# HARPY_SMD.net
KiCad netlist of a schematic drawn in EAGLE
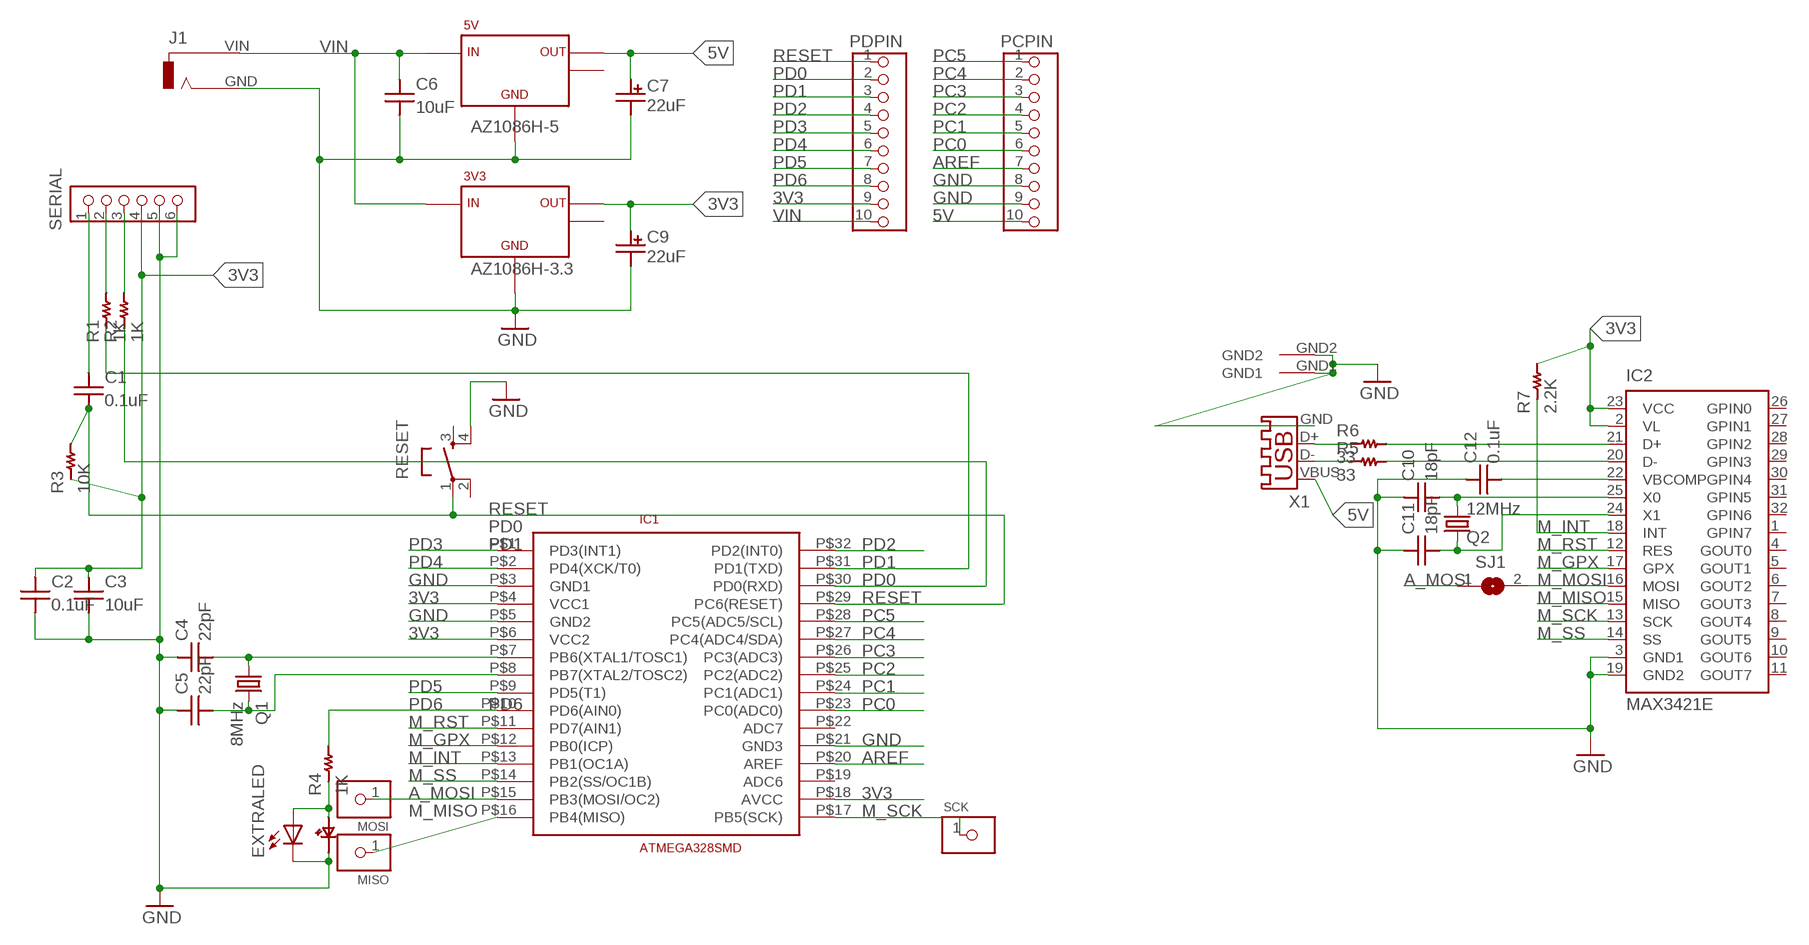
[diagram p0: schematic, sheet 1]

(export (version "E")
  (design (tool "Eeschema 10.0.6"))
  (components
    (comp (ref "3V3")
      (value "AZ1086H")
      (footprint "eagle-import:AZ1086H")
      (libsource (lib "eagle-import") (part "AZ1086H"))
    )
    (comp (ref "5V")
      (value "AZ1086H")
      (footprint "eagle-import:AZ1086H")
      (libsource (lib "eagle-import") (part "AZ1086H"))
    )
    (comp (ref "C1")
      (value "0.1uF")
      (footprint "eagle-import:SMD_2012_0805")
      (libsource (lib "eagle-import") (part "C_SMD2012"))
    )
    (comp (ref "C2")
      (value "0.1uF")
      (footprint "eagle-import:SMD_2012_0805")
      (libsource (lib "eagle-import") (part "C_SMD2012"))
    )
    (comp (ref "C3")
      (value "10uF")
      (footprint "eagle-import:SMD_2012_0805")
      (libsource (lib "eagle-import") (part "C_SMD2012"))
    )
    (comp (ref "C4")
      (value "22pF")
      (footprint "eagle-import:SMD_2012_0805")
      (libsource (lib "eagle-import") (part "C_SMD2012"))
    )
    (comp (ref "C5")
      (value "22pF")
      (footprint "eagle-import:SMD_2012_0805")
      (libsource (lib "eagle-import") (part "C_SMD2012"))
    )
    (comp (ref "C6")
      (value "10uF")
      (footprint "eagle-import:SMD_3216_1206")
      (libsource (lib "eagle-import") (part "C_SMD3216"))
    )
    (comp (ref "C7")
      (value "22uF")
      (footprint "eagle-import:SMD_3528")
      (libsource (lib "eagle-import") (part "C_SMD_POL3528"))
    )
    (comp (ref "C9")
      (value "22uF")
      (footprint "eagle-import:SMD_3528")
      (libsource (lib "eagle-import") (part "C_SMD_POL3528"))
    )
    (comp (ref "C10")
      (value "18pF")
      (footprint "eagle-import:SMD_2012_0805")
      (libsource (lib "eagle-import") (part "C_SMD2012"))
    )
    (comp (ref "C11")
      (value "18pF")
      (footprint "eagle-import:SMD_2012_0805")
      (libsource (lib "eagle-import") (part "C_SMD2012"))
    )
    (comp (ref "C12")
      (value "0.1uF")
      (footprint "eagle-import:SMD_2012_0805")
      (libsource (lib "eagle-import") (part "C_SMD2012"))
    )
    (comp (ref "EXTRALED")
      (value "LED3MM")
      (footprint "eagle-import:LED3MM")
      (libsource (lib "eagle-import") (part "LED3MM"))
    )
    (comp (ref "IC1")
      (value "ATMEGA328SMD")
      (footprint "eagle-import:ATMEGA328SMD")
      (libsource (lib "eagle-import") (part "ATMEGA328SMD"))
    )
    (comp (ref "IC2")
      (value "MAX3421E")
      (footprint "eagle-import:TQFP44")
      (libsource (lib "eagle-import") (part "2064VET44"))
    )
    (comp (ref "J1")
      (value "DCJ0303")
      (footprint "eagle-import:DCJ0303")
      (libsource (lib "eagle-import") (part "DCJ0303"))
    )
    (comp (ref "LED")
      (value "LED1608")
      (footprint "eagle-import:SMD_1608_0603")
      (libsource (lib "eagle-import") (part "LED1608"))
    )
    (comp (ref "MISO")
      (value "1X0108S")
      (footprint "eagle-import:1X01_0.8_UNSIGNED_SQUARE")
      (libsource (lib "eagle-import") (part "1X0108S"))
    )
    (comp (ref "MOSI")
      (value "1X0108S")
      (footprint "eagle-import:1X01_0.8_UNSIGNED_SQUARE")
      (libsource (lib "eagle-import") (part "1X0108S"))
    )
    (comp (ref "PCPIN")
      (value "1X10")
      (footprint "eagle-import:1X10_1.1_UNSIGNED")
      (libsource (lib "eagle-import") (part "1X10"))
    )
    (comp (ref "PDPIN")
      (value "1X10")
      (footprint "eagle-import:1X10_1.1_UNSIGNED")
      (libsource (lib "eagle-import") (part "1X10"))
    )
    (comp (ref "Q1")
      (value "8MHz")
      (footprint "eagle-import:HC49U-V")
      (libsource (lib "eagle-import") (part "CRYSTALHC49U-V"))
    )
    (comp (ref "Q2")
      (value "12MHz")
      (footprint "eagle-import:HC49U-V")
      (libsource (lib "eagle-import") (part "CRYSTALHC49U-V"))
    )
    (comp (ref "R1")
      (value "1K")
      (footprint "eagle-import:SMD_2012_0805")
      (libsource (lib "eagle-import") (part "R_SMD2012"))
    )
    (comp (ref "R2")
      (value "1K")
      (footprint "eagle-import:SMD_2012_0805")
      (libsource (lib "eagle-import") (part "R_SMD2012"))
    )
    (comp (ref "R3")
      (value "10K")
      (footprint "eagle-import:SMD_2012_0805")
      (libsource (lib "eagle-import") (part "R_SMD2012"))
    )
    (comp (ref "R4")
      (value "1K")
      (footprint "eagle-import:SMD_2012_0805")
      (libsource (lib "eagle-import") (part "R_SMD2012"))
    )
    (comp (ref "R5")
      (value "33")
      (footprint "eagle-import:SMD_2012_0805")
      (libsource (lib "eagle-import") (part "R_SMD2012"))
    )
    (comp (ref "R6")
      (value "33")
      (footprint "eagle-import:SMD_2012_0805")
      (libsource (lib "eagle-import") (part "R_SMD2012"))
    )
    (comp (ref "R7")
      (value "2.2K")
      (footprint "eagle-import:SMD_2012_0805")
      (libsource (lib "eagle-import") (part "R_SMD2012"))
    )
    (comp (ref "RESET")
      (value "10-XXAKI")
      (footprint "eagle-import:TSKB-2JL")
      (libsource (lib "eagle-import") (part "10-XXAKI"))
    )
    (comp (ref "SCK")
      (value "1X0108S")
      (footprint "eagle-import:1X01_0.8_UNSIGNED_SQUARE")
      (libsource (lib "eagle-import") (part "1X0108S"))
    )
    (comp (ref "SERIAL")
      (value "1X06A")
      (footprint "eagle-import:1X06_1.1_ARROW")
      (libsource (lib "eagle-import") (part "1X06A"))
    )
    (comp (ref "SJ1") (value "SJ") (footprint "eagle-import:SJ") (libsource (lib "eagle-import") (part "SJ")))
    (comp (ref "X1")
      (value "USB-A003")
      (footprint "eagle-import:USB-A003")
      (libsource (lib "eagle-import") (part "USB-A003"))
    )
  )
  (nets
    (net (code "1") (name "/AREF") (class "Default")
      (node (ref "IC1") (pin "P$20") (pinfunction "AREF_P$20") (pintype "bidirectional"))
      (node (ref "PCPIN") (pin "7") (pinfunction "7_7") (pintype "passive"))
    )
    (net (code "2") (name "/A_MOSI") (class "Default")
      (node (ref "IC1") (pin "P$15") (pinfunction "PB3(MOSI/OC2)_P$15") (pintype "bidirectional"))
      (node (ref "MOSI") (pin "1") (pinfunction "1_1") (pintype "passive"))
      (node (ref "SJ1") (pin "1") (pinfunction "1_1") (pintype "passive"))
    )
    (net (code "3") (name "/M_GPX") (class "Default")
      (node (ref "IC1") (pin "P$12") (pinfunction "PB0(ICP)_P$12") (pintype "bidirectional"))
      (node (ref "IC2") (pin "17") (pinfunction "GPX_17") (pintype "bidirectional"))
    )
    (net (code "4") (name "/M_INT") (class "Default")
      (node (ref "IC1") (pin "P$13") (pinfunction "PB1(OC1A)_P$13") (pintype "bidirectional"))
      (node (ref "IC2") (pin "18") (pinfunction "INT_18") (pintype "bidirectional"))
      (node (ref "R7") (pin "P$1") (pinfunction "1_P$1") (pintype "bidirectional"))
    )
    (net (code "5") (name "/M_MISO") (class "Default")
      (node (ref "IC1") (pin "P$16") (pinfunction "PB4(MISO)_P$16") (pintype "bidirectional"))
      (node (ref "IC2") (pin "15") (pinfunction "MISO_15") (pintype "bidirectional"))
      (node (ref "MISO") (pin "1") (pinfunction "1_1") (pintype "passive"))
    )
    (net (code "6") (name "/M_MOSI") (class "Default")
      (node (ref "IC2") (pin "16") (pinfunction "MOSI_16") (pintype "bidirectional"))
      (node (ref "SJ1") (pin "2") (pinfunction "2_2") (pintype "passive"))
    )
    (net (code "7") (name "/M_RST") (class "Default")
      (node (ref "IC1") (pin "P$11") (pinfunction "PD7(AIN1)_P$11") (pintype "bidirectional"))
      (node (ref "IC2") (pin "12") (pinfunction "RES_12") (pintype "bidirectional"))
    )
    (net (code "8") (name "/M_SCK") (class "Default")
      (node (ref "IC1") (pin "P$17") (pinfunction "PB5(SCK)_P$17") (pintype "bidirectional"))
      (node (ref "IC2") (pin "13") (pinfunction "SCK_13") (pintype "bidirectional"))
      (node (ref "SCK") (pin "1") (pinfunction "1_1") (pintype "passive"))
    )
    (net (code "9") (name "/M_SS") (class "Default")
      (node (ref "IC1") (pin "P$14") (pinfunction "PB2(SS/OC1B)_P$14") (pintype "bidirectional"))
      (node (ref "IC2") (pin "14") (pinfunction "SS_14") (pintype "bidirectional"))
    )
    (net (code "10") (name "/PC0") (class "Default")
      (node (ref "IC1") (pin "P$23") (pinfunction "PC0(ADC0)_P$23") (pintype "bidirectional"))
      (node (ref "PCPIN") (pin "6") (pinfunction "6_6") (pintype "passive"))
    )
    (net (code "11") (name "/PC1") (class "Default")
      (node (ref "IC1") (pin "P$24") (pinfunction "PC1(ADC1)_P$24") (pintype "bidirectional"))
      (node (ref "PCPIN") (pin "5") (pinfunction "5_5") (pintype "passive"))
    )
    (net (code "12") (name "/PC2") (class "Default")
      (node (ref "IC1") (pin "P$25") (pinfunction "PC2(ADC2)_P$25") (pintype "bidirectional"))
      (node (ref "PCPIN") (pin "4") (pinfunction "4_4") (pintype "passive"))
    )
    (net (code "13") (name "/PC3") (class "Default")
      (node (ref "IC1") (pin "P$26") (pinfunction "PC3(ADC3)_P$26") (pintype "bidirectional"))
      (node (ref "PCPIN") (pin "3") (pinfunction "3_3") (pintype "passive"))
    )
    (net (code "14") (name "/PC4") (class "Default")
      (node (ref "IC1") (pin "P$27") (pinfunction "PC4(ADC4/SDA)_P$27") (pintype "bidirectional"))
      (node (ref "PCPIN") (pin "2") (pinfunction "2_2") (pintype "passive"))
    )
    (net (code "15") (name "/PC5") (class "Default")
      (node (ref "IC1") (pin "P$28") (pinfunction "PC5(ADC5/SCL)_P$28") (pintype "bidirectional"))
      (node (ref "PCPIN") (pin "1") (pinfunction "1_1") (pintype "passive"))
    )
    (net (code "16") (name "/PD0") (class "Default")
      (node (ref "IC1") (pin "P$30") (pinfunction "PD0(RXD)_P$30") (pintype "bidirectional"))
      (node (ref "PDPIN") (pin "2") (pinfunction "2_2") (pintype "passive"))
      (node (ref "R2") (pin "P$1") (pinfunction "1_P$1") (pintype "bidirectional"))
    )
    (net (code "17") (name "/PD1") (class "Default")
      (node (ref "IC1") (pin "P$31") (pinfunction "PD1(TXD)_P$31") (pintype "bidirectional"))
      (node (ref "PDPIN") (pin "3") (pinfunction "3_3") (pintype "passive"))
      (node (ref "R1") (pin "P$1") (pinfunction "1_P$1") (pintype "bidirectional"))
    )
    (net (code "18") (name "/PD2") (class "Default")
      (node (ref "IC1") (pin "P$32") (pinfunction "PD2(INT0)_P$32") (pintype "bidirectional"))
      (node (ref "PDPIN") (pin "4") (pinfunction "4_4") (pintype "passive"))
    )
    (net (code "19") (name "/PD3") (class "Default")
      (node (ref "IC1") (pin "P$1") (pinfunction "PD3(INT1)_P$1") (pintype "bidirectional"))
      (node (ref "PDPIN") (pin "5") (pinfunction "5_5") (pintype "passive"))
    )
    (net (code "20") (name "/PD4") (class "Default")
      (node (ref "IC1") (pin "P$2") (pinfunction "PD4(XCK/T0)_P$2") (pintype "bidirectional"))
      (node (ref "PDPIN") (pin "6") (pinfunction "6_6") (pintype "passive"))
    )
    (net (code "21") (name "/PD5") (class "Default")
      (node (ref "IC1") (pin "P$9") (pinfunction "PD5(T1)_P$9") (pintype "bidirectional"))
      (node (ref "PDPIN") (pin "7") (pinfunction "7_7") (pintype "passive"))
    )
    (net (code "22") (name "/PD6") (class "Default")
      (node (ref "IC1") (pin "P$10") (pinfunction "PD6(AIN0)_P$10") (pintype "bidirectional"))
      (node (ref "PDPIN") (pin "8") (pinfunction "8_8") (pintype "passive"))
      (node (ref "R4") (pin "P$2") (pinfunction "2_P$2") (pintype "bidirectional"))
    )
    (net (code "23") (name "/RESET") (class "Default")
      (node (ref "C1") (pin "P$2") (pinfunction "2_P$2") (pintype "bidirectional"))
      (node (ref "IC1") (pin "P$29") (pinfunction "PC6(RESET)_P$29") (pintype "bidirectional"))
      (node (ref "PDPIN") (pin "1") (pinfunction "1_1") (pintype "passive"))
      (node (ref "R3") (pin "P$2") (pinfunction "2_P$2") (pintype "bidirectional"))
      (node (ref "RESET") (pin "1") (pinfunction "P_1") (pintype "passive"))
    )
    (net (code "24") (name "/VIN") (class "Default")
      (node (ref "3V3") (pin "INPUT") (pinfunction "INPUT_INPUT") (pintype "power_in"))
      (node (ref "5V") (pin "INPUT") (pinfunction "INPUT_INPUT") (pintype "power_in"))
      (node (ref "C6") (pin "P$1") (pinfunction "1_P$1") (pintype "bidirectional"))
      (node (ref "J1") (pin "VIN") (pinfunction "VIN_VIN") (pintype "passive"))
      (node (ref "PDPIN") (pin "10") (pinfunction "10_10") (pintype "passive"))
    )
    (net (code "25") (name "3V3") (class "Default")
      (node (ref "3V3") (pin "OUTPUT1") (pinfunction "OUTPUT1_OUTPUT1") (pintype "bidirectional"))
      (node (ref "C2") (pin "P$1") (pinfunction "1_P$1") (pintype "bidirectional"))
      (node (ref "C3") (pin "P$1") (pinfunction "1_P$1") (pintype "bidirectional"))
      (node (ref "C9") (pin "P$1") (pinfunction "+_P$1") (pintype "bidirectional"))
      (node (ref "IC1") (pin "P$18") (pinfunction "AVCC_P$18") (pintype "power_in"))
      (node (ref "IC1") (pin "P$4") (pinfunction "VCC1_P$4") (pintype "power_in"))
      (node (ref "IC1") (pin "P$6") (pinfunction "VCC2_P$6") (pintype "power_in"))
      (node (ref "IC2") (pin "2") (pinfunction "VL_2") (pintype "bidirectional"))
      (node (ref "IC2") (pin "23") (pinfunction "VCC_23") (pintype "bidirectional"))
      (node (ref "PDPIN") (pin "9") (pinfunction "9_9") (pintype "passive"))
      (node (ref "R3") (pin "P$1") (pinfunction "1_P$1") (pintype "bidirectional"))
      (node (ref "R7") (pin "P$2") (pinfunction "2_P$2") (pintype "bidirectional"))
      (node (ref "SERIAL") (pin "4") (pinfunction "4_4") (pintype "passive"))
    )
    (net (code "26") (name "5V") (class "Default")
      (node (ref "5V") (pin "OUTPUT1") (pinfunction "OUTPUT1_OUTPUT1") (pintype "bidirectional"))
      (node (ref "C7") (pin "P$1") (pinfunction "+_P$1") (pintype "bidirectional"))
      (node (ref "PCPIN") (pin "10") (pinfunction "10_10") (pintype "passive"))
      (node (ref "X1") (pin "VBUS") (pinfunction "1_VBUS") (pintype "passive"))
    )
    (net (code "27") (name "GND") (class "Default")
      (node (ref "3V3") (pin "GND") (pinfunction "GND_GND") (pintype "power_in"))
      (node (ref "5V") (pin "GND") (pinfunction "GND_GND") (pintype "power_in"))
      (node (ref "C10") (pin "P$1") (pinfunction "1_P$1") (pintype "bidirectional"))
      (node (ref "C11") (pin "P$1") (pinfunction "1_P$1") (pintype "bidirectional"))
      (node (ref "C12") (pin "P$1") (pinfunction "1_P$1") (pintype "bidirectional"))
      (node (ref "C2") (pin "P$2") (pinfunction "2_P$2") (pintype "bidirectional"))
      (node (ref "C3") (pin "P$2") (pinfunction "2_P$2") (pintype "bidirectional"))
      (node (ref "C4") (pin "P$1") (pinfunction "1_P$1") (pintype "bidirectional"))
      (node (ref "C5") (pin "P$1") (pinfunction "1_P$1") (pintype "bidirectional"))
      (node (ref "C6") (pin "P$2") (pinfunction "2_P$2") (pintype "bidirectional"))
      (node (ref "C7") (pin "P$2") (pinfunction "-_P$2") (pintype "bidirectional"))
      (node (ref "C9") (pin "P$2") (pinfunction "-_P$2") (pintype "bidirectional"))
      (node (ref "EXTRALED") (pin "K") (pinfunction "C_K") (pintype "passive"))
      (node (ref "IC1") (pin "P$21") (pinfunction "GND3_P$21") (pintype "power_in"))
      (node (ref "IC1") (pin "P$3") (pinfunction "GND1_P$3") (pintype "power_in"))
      (node (ref "IC1") (pin "P$5") (pinfunction "GND2_P$5") (pintype "power_in"))
      (node (ref "IC2") (pin "19") (pinfunction "GND2_19") (pintype "bidirectional"))
      (node (ref "IC2") (pin "3") (pinfunction "GND1_3") (pintype "bidirectional"))
      (node (ref "J1") (pin "GND") (pinfunction "GND_GND") (pintype "passive"))
      (node (ref "LED") (pin "P$2") (pinfunction "C_P$2") (pintype "bidirectional"))
      (node (ref "PCPIN") (pin "8") (pinfunction "8_8") (pintype "passive"))
      (node (ref "PCPIN") (pin "9") (pinfunction "9_9") (pintype "passive"))
      (node (ref "RESET") (pin "4") (pinfunction "S1_4") (pintype "passive"))
      (node (ref "SERIAL") (pin "5") (pinfunction "5_5") (pintype "passive"))
      (node (ref "SERIAL") (pin "6") (pinfunction "6_6") (pintype "passive"))
      (node (ref "X1") (pin "GND") (pinfunction "4_GND") (pintype "passive"))
      (node (ref "X1") (pin "GND1") (pinfunction "GND1_GND1") (pintype "power_in"))
      (node (ref "X1") (pin "GND2") (pinfunction "GND2_GND2") (pintype "power_in"))
    )
    (net (code "28") (name "Net-(C1-1)") (class "Default")
      (node (ref "C1") (pin "P$1") (pinfunction "1_P$1") (pintype "bidirectional"))
      (node (ref "SERIAL") (pin "1") (pinfunction "1_1") (pintype "passive"))
    )
    (net (code "29") (name "Net-(C4-2)") (class "Default")
      (node (ref "C4") (pin "P$2") (pinfunction "2_P$2") (pintype "bidirectional"))
      (node (ref "IC1") (pin "P$7") (pinfunction "PB6(XTAL1/TOSC1)_P$7") (pintype "bidirectional"))
      (node (ref "Q1") (pin "1") (pinfunction "1_1") (pintype "passive"))
    )
    (net (code "30") (name "Net-(C5-2)") (class "Default")
      (node (ref "C5") (pin "P$2") (pinfunction "2_P$2") (pintype "bidirectional"))
      (node (ref "IC1") (pin "P$8") (pinfunction "PB7(XTAL2/TOSC2)_P$8") (pintype "bidirectional"))
      (node (ref "Q1") (pin "2") (pinfunction "2_2") (pintype "passive"))
    )
    (net (code "31") (name "Net-(C10-2)") (class "Default")
      (node (ref "C10") (pin "P$2") (pinfunction "2_P$2") (pintype "bidirectional"))
      (node (ref "IC2") (pin "25") (pinfunction "X0_25") (pintype "bidirectional"))
      (node (ref "Q2") (pin "1") (pinfunction "1_1") (pintype "passive"))
    )
    (net (code "32") (name "Net-(C11-2)") (class "Default")
      (node (ref "C11") (pin "P$2") (pinfunction "2_P$2") (pintype "bidirectional"))
      (node (ref "IC2") (pin "24") (pinfunction "X1_24") (pintype "bidirectional"))
      (node (ref "Q2") (pin "2") (pinfunction "2_2") (pintype "passive"))
    )
    (net (code "33") (name "Net-(C12-2)") (class "Default")
      (node (ref "C12") (pin "P$2") (pinfunction "2_P$2") (pintype "bidirectional"))
      (node (ref "IC2") (pin "22") (pinfunction "VBCOMP_22") (pintype "bidirectional"))
    )
    (net (code "34") (name "Net-(IC2-D+)") (class "Default")
      (node (ref "IC2") (pin "21") (pinfunction "D+_21") (pintype "bidirectional"))
      (node (ref "R6") (pin "P$2") (pinfunction "2_P$2") (pintype "bidirectional"))
    )
    (net (code "35") (name "Net-(IC2-D-)") (class "Default")
      (node (ref "IC2") (pin "20") (pinfunction "D-_20") (pintype "bidirectional"))
      (node (ref "R5") (pin "P$2") (pinfunction "2_P$2") (pintype "bidirectional"))
    )
    (net (code "36") (name "Net-(LED-A)") (class "Default")
      (node (ref "EXTRALED") (pin "A") (pinfunction "A_A") (pintype "passive"))
      (node (ref "LED") (pin "P$1") (pinfunction "A_P$1") (pintype "bidirectional"))
      (node (ref "R4") (pin "P$1") (pinfunction "1_P$1") (pintype "bidirectional"))
    )
    (net (code "37") (name "Net-(R1-2)") (class "Default")
      (node (ref "R1") (pin "P$2") (pinfunction "2_P$2") (pintype "bidirectional"))
      (node (ref "SERIAL") (pin "2") (pinfunction "2_2") (pintype "passive"))
    )
    (net (code "38") (name "Net-(R2-2)") (class "Default")
      (node (ref "R2") (pin "P$2") (pinfunction "2_P$2") (pintype "bidirectional"))
      (node (ref "SERIAL") (pin "3") (pinfunction "3_3") (pintype "passive"))
    )
    (net (code "39") (name "Net-(R5-1)") (class "Default")
      (node (ref "R5") (pin "P$1") (pinfunction "1_P$1") (pintype "bidirectional"))
      (node (ref "X1") (pin "D-") (pinfunction "2_D-") (pintype "passive"))
    )
    (net (code "40") (name "Net-(R6-1)") (class "Default")
      (node (ref "R6") (pin "P$1") (pinfunction "1_P$1") (pintype "bidirectional"))
      (node (ref "X1") (pin "D+") (pinfunction "3_D+") (pintype "passive"))
    )
    (net (code "41") (name "unconnected-(3V3-PadOUTPUT2)") (class "Default")
      (node (ref "3V3") (pin "OUTPUT2") (pinfunction "OUTPUT2_OUTPUT2") (pintype "bidirectional"))
    )
    (net (code "42") (name "unconnected-(5V-PadOUTPUT2)") (class "Default")
      (node (ref "5V") (pin "OUTPUT2") (pinfunction "OUTPUT2_OUTPUT2") (pintype "bidirectional"))
    )
    (net (code "43") (name "unconnected-(IC1-ADC6-PadP$19)") (class "Default")
      (node (ref "IC1") (pin "P$19") (pinfunction "ADC6_P$19") (pintype "bidirectional"))
    )
    (net (code "44") (name "unconnected-(IC1-ADC7-PadP$22)") (class "Default")
      (node (ref "IC1") (pin "P$22") (pinfunction "ADC7_P$22") (pintype "bidirectional"))
    )
    (net (code "45") (name "unconnected-(IC2-GOUT0-Pad4)") (class "Default")
      (node (ref "IC2") (pin "4") (pinfunction "GOUT0_4") (pintype "bidirectional"))
    )
    (net (code "46") (name "unconnected-(IC2-GOUT1-Pad5)") (class "Default")
      (node (ref "IC2") (pin "5") (pinfunction "GOUT1_5") (pintype "bidirectional"))
    )
    (net (code "47") (name "unconnected-(IC2-GOUT2-Pad6)") (class "Default")
      (node (ref "IC2") (pin "6") (pinfunction "GOUT2_6") (pintype "bidirectional"))
    )
    (net (code "48") (name "unconnected-(IC2-GOUT3-Pad7)") (class "Default")
      (node (ref "IC2") (pin "7") (pinfunction "GOUT3_7") (pintype "bidirectional"))
    )
    (net (code "49") (name "unconnected-(IC2-GOUT4-Pad8)") (class "Default")
      (node (ref "IC2") (pin "8") (pinfunction "GOUT4_8") (pintype "bidirectional"))
    )
    (net (code "50") (name "unconnected-(IC2-GOUT5-Pad9)") (class "Default")
      (node (ref "IC2") (pin "9") (pinfunction "GOUT5_9") (pintype "bidirectional"))
    )
    (net (code "51") (name "unconnected-(IC2-GOUT6-Pad10)") (class "Default")
      (node (ref "IC2") (pin "10") (pinfunction "GOUT6_10") (pintype "bidirectional"))
    )
    (net (code "52") (name "unconnected-(IC2-GOUT7-Pad11)") (class "Default")
      (node (ref "IC2") (pin "11") (pinfunction "GOUT7_11") (pintype "bidirectional"))
    )
    (net (code "53") (name "unconnected-(IC2-GPIN0-Pad26)") (class "Default")
      (node (ref "IC2") (pin "26") (pinfunction "GPIN0_26") (pintype "bidirectional"))
    )
    (net (code "54") (name "unconnected-(IC2-GPIN1-Pad27)") (class "Default")
      (node (ref "IC2") (pin "27") (pinfunction "GPIN1_27") (pintype "bidirectional"))
    )
    (net (code "55") (name "unconnected-(IC2-GPIN2-Pad28)") (class "Default")
      (node (ref "IC2") (pin "28") (pinfunction "GPIN2_28") (pintype "bidirectional"))
    )
    (net (code "56") (name "unconnected-(IC2-GPIN3-Pad29)") (class "Default")
      (node (ref "IC2") (pin "29") (pinfunction "GPIN3_29") (pintype "bidirectional"))
    )
    (net (code "57") (name "unconnected-(IC2-GPIN4-Pad30)") (class "Default")
      (node (ref "IC2") (pin "30") (pinfunction "GPIN4_30") (pintype "bidirectional"))
    )
    (net (code "58") (name "unconnected-(IC2-GPIN5-Pad31)") (class "Default")
      (node (ref "IC2") (pin "31") (pinfunction "GPIN5_31") (pintype "bidirectional"))
    )
    (net (code "59") (name "unconnected-(IC2-GPIN6-Pad32)") (class "Default")
      (node (ref "IC2") (pin "32") (pinfunction "GPIN6_32") (pintype "bidirectional"))
    )
    (net (code "60") (name "unconnected-(IC2-GPIN7-Pad1)") (class "Default")
      (node (ref "IC2") (pin "1") (pinfunction "GPIN7_1") (pintype "bidirectional"))
    )
    (net (code "61") (name "unconnected-(RESET-P1-Pad2)") (class "Default")
      (node (ref "RESET") (pin "2") (pinfunction "P1_2") (pintype "passive"))
    )
    (net (code "62") (name "unconnected-(RESET-S-Pad3)") (class "Default")
      (node (ref "RESET") (pin "3") (pinfunction "S_3") (pintype "passive"))
    )
  )
)
